# design.net
KiCad netlist of a schematic drawn in Altium Designer
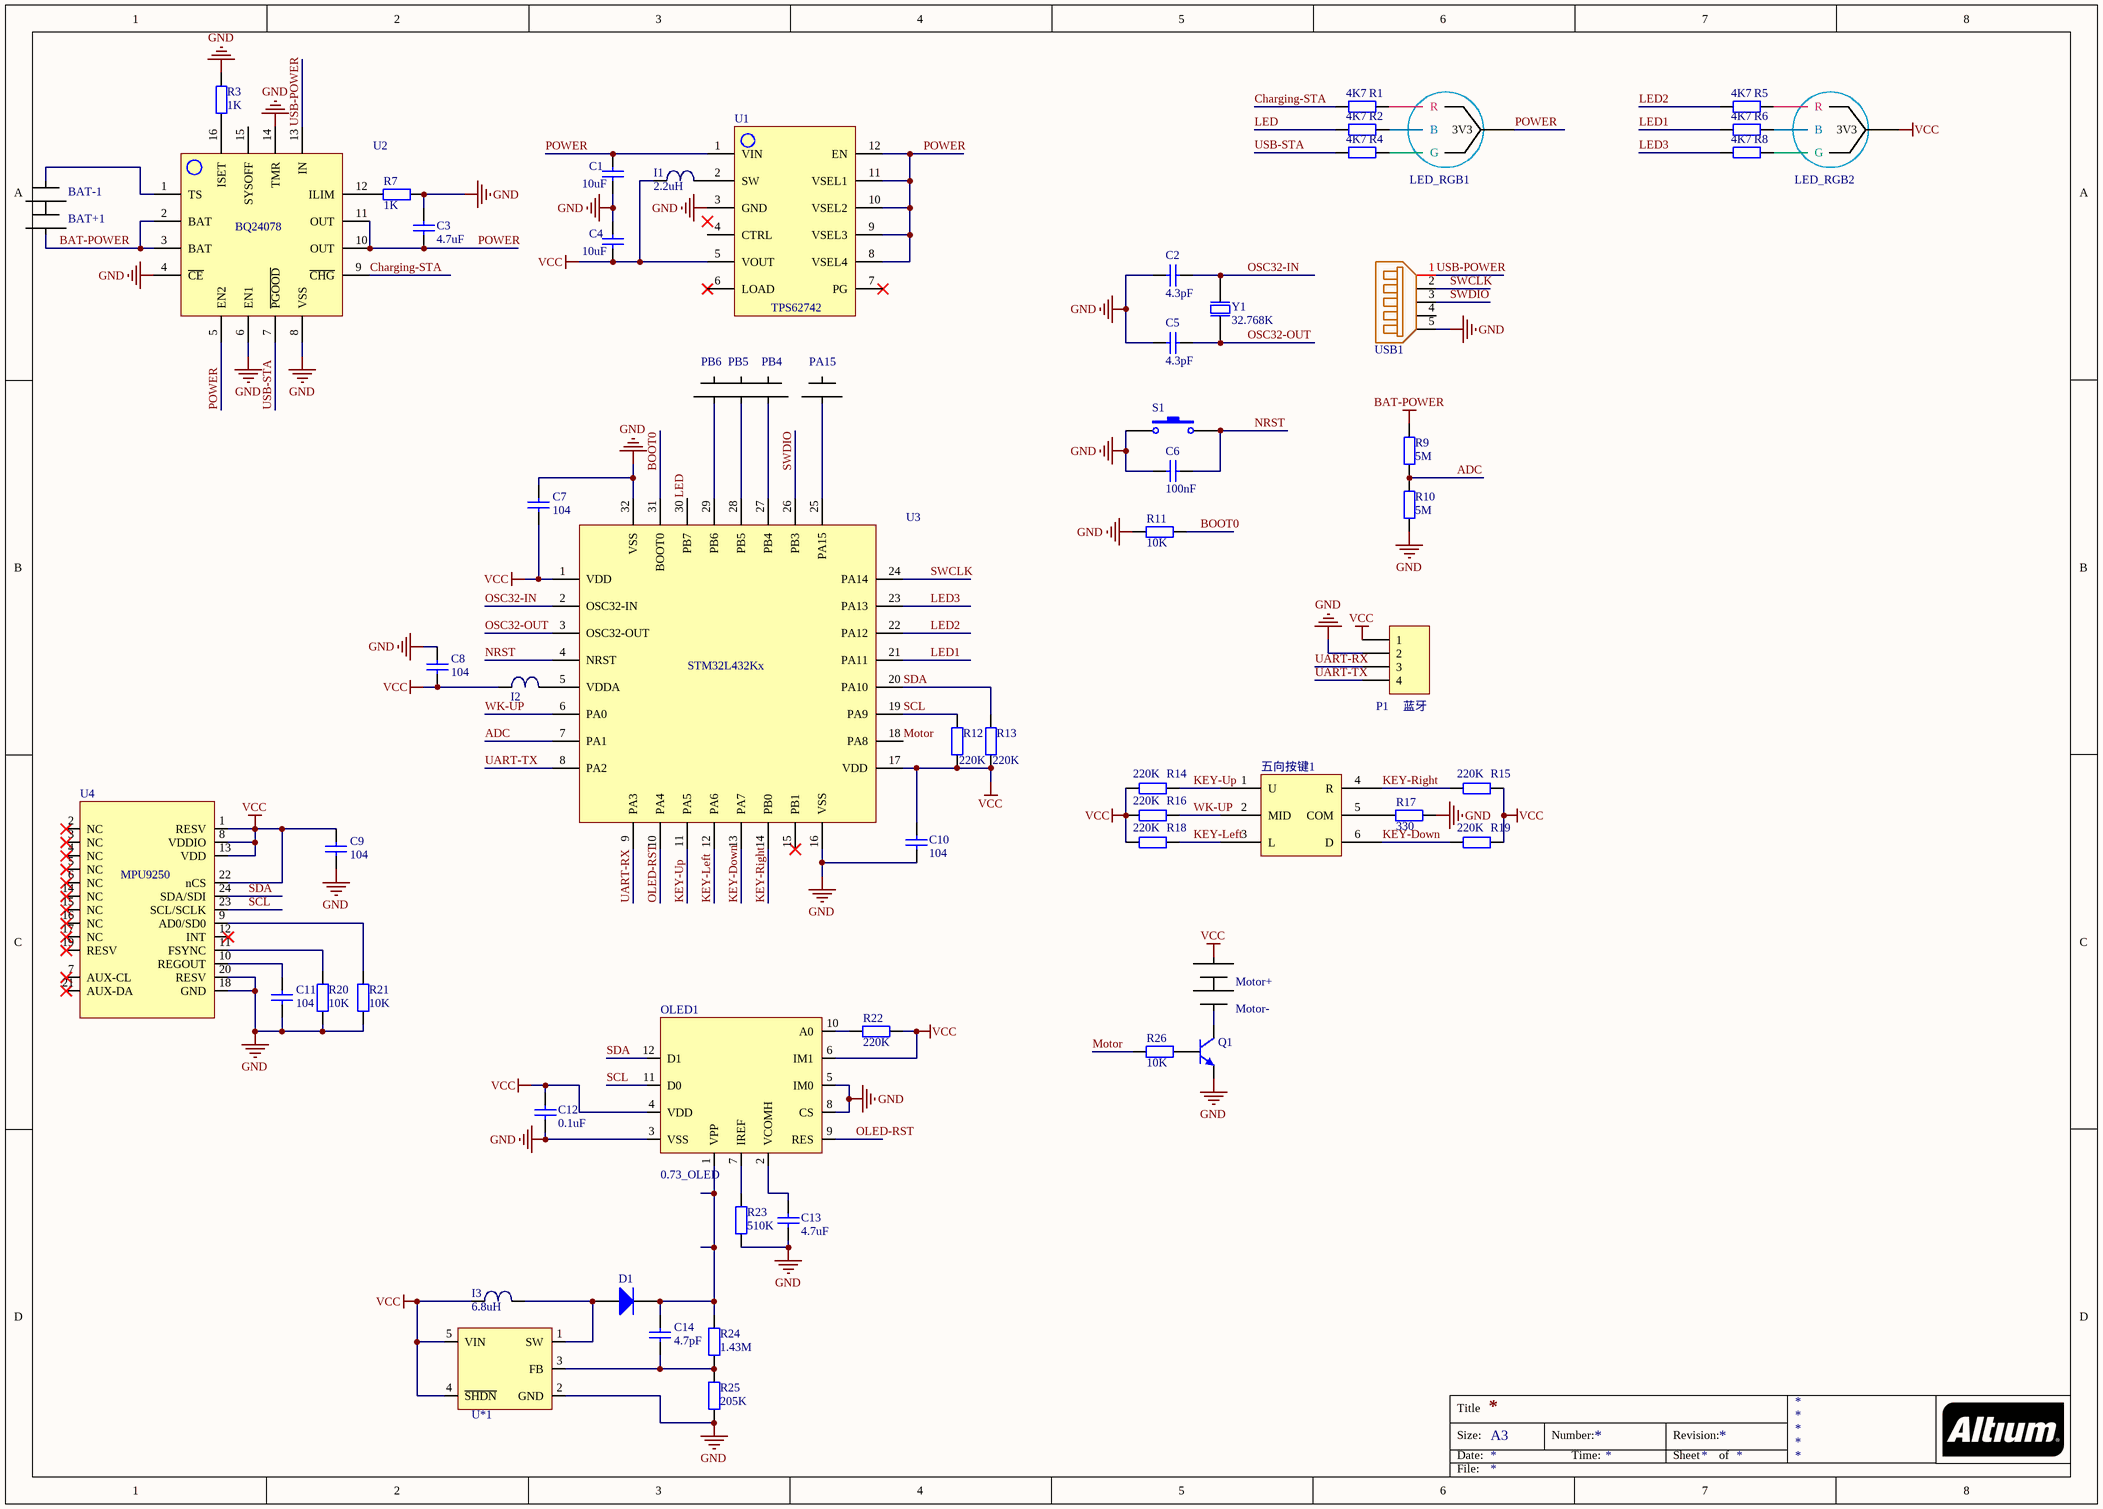
[diagram p0: 原理图.SchDoc]

(export (version "E")
  (design (tool "Eeschema 10.0.6"))
  (components
    (comp (ref "BAT+1") (value "BAT") (footprint "BAT+") (libsource (lib "原理图库") (part "BAT")))
    (comp (ref "BAT-1") (value "BAT") (footprint "BTA-") (libsource (lib "原理图库") (part "BAT")))
    (comp (ref "C1")
      (value "10uF")
      (footprint "1__0603-CAP_")
      (description "Capacitor")
      (libsource (lib "Miscellaneous Devices") (part "Cap"))
    )
    (comp (ref "C2")
      (value "4.3pF")
      (footprint "1__0603-CAP_")
      (description "Capacitor")
      (libsource (lib "Miscellaneous Devices") (part "Cap"))
    )
    (comp (ref "C3")
      (value "4.7uF")
      (footprint "1__0603-CAP_")
      (description "Capacitor")
      (libsource (lib "Miscellaneous Devices") (part "Cap"))
    )
    (comp (ref "C4")
      (value "10uF")
      (footprint "1__0603-CAP_")
      (description "Capacitor")
      (libsource (lib "Miscellaneous Devices") (part "Cap"))
    )
    (comp (ref "C5")
      (value "4.3pF")
      (footprint "1__0603-CAP_")
      (description "Capacitor")
      (libsource (lib "Miscellaneous Devices") (part "Cap"))
    )
    (comp (ref "C6")
      (value "100nF")
      (footprint "1__0603-CAP_")
      (description "Capacitor")
      (libsource (lib "Miscellaneous Devices") (part "Cap"))
    )
    (comp (ref "C7")
      (value "104")
      (footprint "1__0603-CAP_")
      (description "Capacitor")
      (libsource (lib "Miscellaneous Devices") (part "Cap"))
    )
    (comp (ref "C8")
      (value "104")
      (footprint "1__0603-CAP_")
      (description "Capacitor")
      (libsource (lib "Miscellaneous Devices") (part "Cap"))
    )
    (comp (ref "C9")
      (value "104")
      (footprint "1__0603-CAP_")
      (description "Capacitor")
      (libsource (lib "Miscellaneous Devices") (part "Cap"))
    )
    (comp (ref "C10")
      (value "104")
      (footprint "1__0603-CAP_")
      (description "Capacitor")
      (libsource (lib "Miscellaneous Devices") (part "Cap"))
    )
    (comp (ref "C11")
      (value "104")
      (footprint "1__0603-CAP_")
      (description "Capacitor")
      (libsource (lib "Miscellaneous Devices") (part "Cap"))
    )
    (comp (ref "C12")
      (value "0.1uF")
      (footprint "1__0603-CAP_")
      (description "Capacitor")
      (libsource (lib "Miscellaneous Devices") (part "Cap"))
    )
    (comp (ref "C13")
      (value "4.7uF")
      (footprint "1__0603-CAP_")
      (description "Capacitor")
      (libsource (lib "Miscellaneous Devices") (part "Cap"))
    )
    (comp (ref "C14")
      (value "4.7pF")
      (footprint "1__0603-CAP_")
      (description "Capacitor")
      (libsource (lib "Miscellaneous Devices") (part "Cap"))
    )
    (comp (ref "D1")
      (value "Diode")
      (footprint "二极管1206")
      (description "Default Diode")
      (fields (field (name "PUBLISHER") "Altium Limited"))
      (libsource (lib "Miscellaneous Devices") (part "Diode"))
    )
    (comp (ref "I1") (value "2.2uH") (footprint "1__0805_IND") (libsource (lib "常用原理图_by_K") (part "电感")))
    (comp (ref "I2") (value "100uH") (footprint "1__0603_Ind_") (libsource (lib "常用原理图_by_K") (part "电感")))
    (comp (ref "I3") (value "6.8uH") (footprint "0805_Ind") (libsource (lib "常用原理图_by_K") (part "电感")))
    (comp (ref "LED_RGB1")
      (value "L*")
      (footprint "1__LED_RGB")
      (libsource (lib "MotherBoard_Prototype") (part "LED_RGB"))
    )
    (comp (ref "LED_RGB2")
      (value "L*")
      (footprint "1__LED_RGB")
      (libsource (lib "MotherBoard_Prototype") (part "LED_RGB"))
    )
    (comp (ref "Motor+") (value "BAT") (footprint "BAT+") (libsource (lib "原理图库") (part "BAT")))
    (comp (ref "Motor-") (value "BAT") (footprint "BTA-") (libsource (lib "原理图库") (part "BAT")))
    (comp (ref "OLED1")
      (value "0.73_OLED")
      (footprint "0.73OLED")
      (libsource (lib "原理图库") (part "0.73_OLED"))
    )
    (comp (ref "P1")
      (value "蓝牙")
      (footprint "BT")
      (description "Header, 4-Pin")
      (libsource (lib "!)Miscellaneous Integrated Library") (part "Header 4"))
    )
    (comp (ref "PA15") (value "BAT") (footprint "BAT+") (libsource (lib "原理图库") (part "BAT")))
    (comp (ref "PB4") (value "BAT") (footprint "BAT+") (libsource (lib "原理图库") (part "BAT")))
    (comp (ref "PB5") (value "BAT") (footprint "BAT+") (libsource (lib "原理图库") (part "BAT")))
    (comp (ref "PB6") (value "BAT") (footprint "BAT+") (libsource (lib "原理图库") (part "BAT")))
    (comp (ref "Q1")
      (value "NPN-J3Y/Y1")
      (footprint "SOT23")
      (description "NPN Bipolar Transistor")
      (fields (field (name "PARTNUMBER") "BC817-40") (field (name "PUBLISHER") "Altium Limited"))
      (libsource (lib "!)Miscellaneous Integrated Library") (part "NPN BC817-40"))
    )
    (comp (ref "R1")
      (value "4K7")
      (footprint "1__0603-RES_")
      (description "Resistor")
      (libsource (lib "") (part "Res2_1"))
    )
    (comp (ref "R2")
      (value "4K7")
      (footprint "1__0603-RES_")
      (description "Resistor")
      (libsource (lib "") (part "Res2_1"))
    )
    (comp (ref "R3")
      (value "1K")
      (footprint "1__0603-RES_")
      (description "Resistor")
      (libsource (lib "Miscellaneous Devices") (part "Res2"))
    )
    (comp (ref "R4")
      (value "4K7")
      (footprint "1__0603-RES_")
      (description "Resistor")
      (libsource (lib "") (part "Res2_1"))
    )
    (comp (ref "R5")
      (value "4K7")
      (footprint "1__0603-RES_")
      (description "Resistor")
      (libsource (lib "") (part "Res2_1"))
    )
    (comp (ref "R6")
      (value "4K7")
      (footprint "1__0603-RES_")
      (description "Resistor")
      (libsource (lib "") (part "Res2_1"))
    )
    (comp (ref "R7")
      (value "1K")
      (footprint "1__0603-RES_")
      (description "Resistor")
      (libsource (lib "") (part "Res2_1"))
    )
    (comp (ref "R8")
      (value "4K7")
      (footprint "1__0603-RES_")
      (description "Resistor")
      (libsource (lib "") (part "Res2_1"))
    )
    (comp (ref "R9")
      (value "5M")
      (footprint "1__0603-RES_")
      (description "Resistor")
      (libsource (lib "Miscellaneous Devices") (part "Res2"))
    )
    (comp (ref "R10")
      (value "5M")
      (footprint "1__0603-RES_")
      (description "Resistor")
      (libsource (lib "Miscellaneous Devices") (part "Res2"))
    )
    (comp (ref "R11")
      (value "10K")
      (footprint "1__0603-RES_")
      (description "Resistor")
      (libsource (lib "") (part "Res2_1"))
    )
    (comp (ref "R12")
      (value "220K")
      (footprint "1__0603-RES_")
      (description "Resistor")
      (libsource (lib "") (part "Res2_3"))
    )
    (comp (ref "R13")
      (value "220K")
      (footprint "1__0603-RES_")
      (description "Resistor")
      (libsource (lib "") (part "Res2_3"))
    )
    (comp (ref "R14")
      (value "220K")
      (footprint "1__0603-RES_")
      (description "Resistor")
      (libsource (lib "") (part "Res2_2"))
    )
    (comp (ref "R15")
      (value "220K")
      (footprint "1__0603-RES_")
      (description "Resistor")
      (libsource (lib "") (part "Res2_2"))
    )
    (comp (ref "R16")
      (value "220K")
      (footprint "1__0603-RES_")
      (description "Resistor")
      (libsource (lib "") (part "Res2_2"))
    )
    (comp (ref "R17")
      (value "330")
      (footprint "1__0603-RES_")
      (description "Resistor")
      (libsource (lib "") (part "Res2_1"))
    )
    (comp (ref "R18")
      (value "220K")
      (footprint "1__0603-RES_")
      (description "Resistor")
      (libsource (lib "") (part "Res2_2"))
    )
    (comp (ref "R19")
      (value "220K")
      (footprint "1__0603-RES_")
      (description "Resistor")
      (libsource (lib "") (part "Res2_2"))
    )
    (comp (ref "R20")
      (value "10K")
      (footprint "1__0603-RES_")
      (description "Resistor")
      (libsource (lib "") (part "Res2_3"))
    )
    (comp (ref "R21")
      (value "10K")
      (footprint "1__0603-RES_")
      (description "Resistor")
      (libsource (lib "") (part "Res2_3"))
    )
    (comp (ref "R22")
      (value "220K")
      (footprint "1__0603-RES_")
      (description "Resistor")
      (libsource (lib "") (part "Res2_2"))
    )
    (comp (ref "R23")
      (value "510K")
      (footprint "1__0603-RES_")
      (description "Resistor")
      (libsource (lib "Miscellaneous Devices") (part "Res2"))
    )
    (comp (ref "R24")
      (value "1.43M")
      (footprint "1__0603-RES_")
      (description "Resistor")
      (libsource (lib "Miscellaneous Devices") (part "Res2"))
    )
    (comp (ref "R25")
      (value "205K")
      (footprint "1__0603-RES_")
      (description "Resistor")
      (libsource (lib "Miscellaneous Devices") (part "Res2"))
    )
    (comp (ref "R26")
      (value "10K")
      (footprint "1__0603-RES_")
      (description "Resistor")
      (libsource (lib "") (part "Res2_1"))
    )
    (comp (ref "S1")
      (value "~")
      (footprint "key3*4*2")
      (description "Switch")
      (libsource (lib "Miscellaneous Devices") (part "SW-PB"))
    )
    (comp (ref "U*1") (value "OLED升压") (footprint "1__SOT23-5") (libsource (lib "原理图库") (part "TPS61040")))
    (comp (ref "U1")
      (value "TPS62742")
      (footprint "TPS62742")
      (description "锂电池稳压")
      (libsource (lib "原理图库") (part "TPS62742"))
    )
    (comp (ref "U2")
      (value "BQ24078")
      (footprint "BQ24078")
      (description "充电芯片")
      (libsource (lib "原理图库") (part "BQ24078"))
    )
    (comp (ref "U3")
      (value "STM32L432Kx")
      (footprint "STM32L432")
      (description "单片机")
      (libsource (lib "原理图库") (part "STM32L432Kx"))
    )
    (comp (ref "U4")
      (value "MPU9250")
      (footprint "1__QFN3*3 (改1)")
      (libsource (lib "Schlib1") (part "MPU9250"))
    )
    (comp (ref "USB1")
      (value "USB-5P")
      (footprint "1__Micro USB 立贴_")
      (description "USB CONNECTOR")
      (libsource (lib "!)Miscellaneous Integrated Library") (part "USB-5P"))
    )
    (comp (ref "Y1")
      (value "32.768K")
      (footprint "OSC32")
      (description "Crystal Oscillator")
      (libsource (lib "!)Miscellaneous Integrated Library") (part "XTAL"))
    )
    (comp (ref "五向按键1") (value "五向按键") (footprint "1__五向按键_") (libsource (lib "没有的器件原理图") (part "五向按键")))
  )
  (nets
    (net (code "2") (name "/ADC") (class "Default")
      (node (ref "R10") (pin "1") (pinfunction "1_1") (pintype "passive"))
      (node (ref "R9") (pin "2") (pinfunction "2_2") (pintype "passive"))
      (node (ref "U3") (pin "7") (pinfunction "PA1_7") (pintype "passive"))
    )
    (net (code "3") (name "/BOOT0") (class "Default")
      (node (ref "R11") (pin "1") (pinfunction "1_1") (pintype "passive"))
      (node (ref "U3") (pin "31") (pinfunction "BOOT0_31") (pintype "passive"))
    )
    (net (code "4") (name "/Charging-STA") (class "Default")
      (node (ref "R1") (pin "2") (pinfunction "2_2") (pintype "passive"))
      (node (ref "U2") (pin "9") (pinfunction "~{CHG}_9") (pintype "passive"))
    )
    (net (code "5") (name "/KEY-Down") (class "Default")
      (node (ref "R19") (pin "1") (pinfunction "1_1") (pintype "passive"))
      (node (ref "U3") (pin "13") (pinfunction "PA7_13") (pintype "passive"))
      (node (ref "五向按键1") (pin "6") (pinfunction "D_6") (pintype "passive"))
    )
    (net (code "6") (name "/KEY-Left") (class "Default")
      (node (ref "R18") (pin "2") (pinfunction "2_2") (pintype "passive"))
      (node (ref "U3") (pin "12") (pinfunction "PA6_12") (pintype "passive"))
      (node (ref "五向按键1") (pin "3") (pinfunction "L_3") (pintype "passive"))
    )
    (net (code "7") (name "/KEY-Right") (class "Default")
      (node (ref "R15") (pin "1") (pinfunction "1_1") (pintype "passive"))
      (node (ref "U3") (pin "14") (pinfunction "PB0_14") (pintype "passive"))
      (node (ref "五向按键1") (pin "4") (pinfunction "R_4") (pintype "passive"))
    )
    (net (code "8") (name "/KEY-Up") (class "Default")
      (node (ref "R14") (pin "2") (pinfunction "2_2") (pintype "passive"))
      (node (ref "U3") (pin "11") (pinfunction "PA5_11") (pintype "passive"))
      (node (ref "五向按键1") (pin "1") (pinfunction "U_1") (pintype "passive"))
    )
    (net (code "9") (name "/LED") (class "Default")
      (node (ref "R2") (pin "2") (pinfunction "2_2") (pintype "passive"))
      (node (ref "U3") (pin "30") (pinfunction "PB7_30") (pintype "passive"))
    )
    (net (code "10") (name "/LED1") (class "Default")
      (node (ref "R6") (pin "2") (pinfunction "2_2") (pintype "passive"))
      (node (ref "U3") (pin "21") (pinfunction "PA11_21") (pintype "passive"))
    )
    (net (code "11") (name "/LED2") (class "Default")
      (node (ref "R5") (pin "2") (pinfunction "2_2") (pintype "passive"))
      (node (ref "U3") (pin "22") (pinfunction "PA12_22") (pintype "passive"))
    )
    (net (code "12") (name "/LED3") (class "Default")
      (node (ref "R8") (pin "2") (pinfunction "2_2") (pintype "passive"))
      (node (ref "U3") (pin "23") (pinfunction "PA13_23") (pintype "passive"))
    )
    (net (code "13") (name "/Motor") (class "Default")
      (node (ref "R26") (pin "2") (pinfunction "2_2") (pintype "passive"))
      (node (ref "U3") (pin "18") (pinfunction "PA8_18") (pintype "passive"))
    )
    (net (code "14") (name "/NRST") (class "Default")
      (node (ref "C6") (pin "2") (pinfunction "2_2") (pintype "passive"))
      (node (ref "S1") (pin "2") (pinfunction "2_2") (pintype "passive"))
      (node (ref "U3") (pin "4") (pinfunction "NRST_4") (pintype "passive"))
    )
    (net (code "15") (name "/OLED-RST") (class "Default")
      (node (ref "OLED1") (pin "9") (pinfunction "RES_9") (pintype "passive"))
      (node (ref "U3") (pin "10") (pinfunction "PA4_10") (pintype "passive"))
    )
    (net (code "16") (name "/OSC32-IN") (class "Default")
      (node (ref "C2") (pin "1") (pinfunction "1_1") (pintype "passive"))
      (node (ref "U3") (pin "2") (pinfunction "OSC32-IN_2") (pintype "passive"))
      (node (ref "Y1") (pin "2") (pinfunction "OSC2_2") (pintype "passive"))
    )
    (net (code "17") (name "/OSC32-OUT") (class "Default")
      (node (ref "C5") (pin "1") (pinfunction "1_1") (pintype "passive"))
      (node (ref "U3") (pin "3") (pinfunction "OSC32-OUT_3") (pintype "passive"))
      (node (ref "Y1") (pin "1") (pinfunction "OSC1_1") (pintype "passive"))
    )
    (net (code "18") (name "/POWER") (class "Default")
      (node (ref "C1") (pin "2") (pinfunction "2_2") (pintype "passive"))
      (node (ref "C3") (pin "1") (pinfunction "1_1") (pintype "passive"))
      (node (ref "LED_RGB1") (pin "2") (pinfunction "3V3_2") (pintype "passive"))
      (node (ref "U1") (pin "1") (pinfunction "VIN_1") (pintype "passive"))
      (node (ref "U1") (pin "10") (pinfunction "VSEL2_10") (pintype "passive"))
      (node (ref "U1") (pin "11") (pinfunction "VSEL1_11") (pintype "passive"))
      (node (ref "U1") (pin "12") (pinfunction "EN_12") (pintype "passive"))
      (node (ref "U1") (pin "8") (pinfunction "VSEL4_8") (pintype "passive"))
      (node (ref "U1") (pin "9") (pinfunction "VSEL3_9") (pintype "passive"))
      (node (ref "U2") (pin "10") (pinfunction "OUT_10") (pintype "passive"))
      (node (ref "U2") (pin "11") (pinfunction "OUT_11") (pintype "passive"))
      (node (ref "U2") (pin "5") (pinfunction "EN2_5") (pintype "passive"))
    )
    (net (code "19") (name "/SCL") (class "Default")
      (node (ref "OLED1") (pin "11") (pinfunction "D0_11") (pintype "passive"))
      (node (ref "R12") (pin "2") (pinfunction "2_2") (pintype "passive"))
      (node (ref "U3") (pin "19") (pinfunction "PA9_19") (pintype "passive"))
      (node (ref "U4") (pin "23") (pinfunction "SCL/SCLK_23") (pintype "passive"))
    )
    (net (code "20") (name "/SDA") (class "Default")
      (node (ref "OLED1") (pin "12") (pinfunction "D1_12") (pintype "passive"))
      (node (ref "R13") (pin "2") (pinfunction "2_2") (pintype "passive"))
      (node (ref "U3") (pin "20") (pinfunction "PA10_20") (pintype "passive"))
      (node (ref "U4") (pin "24") (pinfunction "SDA/SDI_24") (pintype "passive"))
    )
    (net (code "21") (name "/SWCLK") (class "Default")
      (node (ref "U3") (pin "24") (pinfunction "PA14_24") (pintype "passive"))
      (node (ref "USB1") (pin "2") (pinfunction "D-_2") (pintype "passive"))
    )
    (net (code "22") (name "/SWDIO") (class "Default")
      (node (ref "U3") (pin "26") (pinfunction "PB3_26") (pintype "passive"))
      (node (ref "USB1") (pin "3") (pinfunction "D+_3") (pintype "passive"))
    )
    (net (code "23") (name "/UART-RX") (class "Default")
      (node (ref "P1") (pin "3") (pinfunction "3_3") (pintype "passive"))
      (node (ref "U3") (pin "9") (pinfunction "PA3_9") (pintype "passive"))
    )
    (net (code "24") (name "/UART-TX") (class "Default")
      (node (ref "P1") (pin "4") (pinfunction "4_4") (pintype "passive"))
      (node (ref "U3") (pin "8") (pinfunction "PA2_8") (pintype "passive"))
    )
    (net (code "25") (name "/USB-POWER") (class "Default")
      (node (ref "U2") (pin "13") (pinfunction "IN_13") (pintype "passive"))
      (node (ref "USB1") (pin "1") (pinfunction "VBUS_1") (pintype "passive"))
    )
    (net (code "26") (name "/USB-STA") (class "Default")
      (node (ref "R4") (pin "2") (pinfunction "2_2") (pintype "passive"))
      (node (ref "U2") (pin "7") (pinfunction "~{PGOOD}_7") (pintype "passive"))
    )
    (net (code "27") (name "/WK-UP") (class "Default")
      (node (ref "R16") (pin "2") (pinfunction "2_2") (pintype "passive"))
      (node (ref "U3") (pin "6") (pinfunction "PA0_6") (pintype "passive"))
      (node (ref "五向按键1") (pin "2") (pinfunction "MID_2") (pintype "passive"))
    )
    (net (code "28") (name "BAT-POWER") (class "Default")
      (node (ref "BAT+1") (pin "1") (pintype "passive"))
      (node (ref "R9") (pin "1") (pinfunction "1_1") (pintype "passive"))
      (node (ref "U2") (pin "2") (pinfunction "BAT_2") (pintype "passive"))
      (node (ref "U2") (pin "3") (pinfunction "BAT_3") (pintype "passive"))
    )
    (net (code "29") (name "GND") (class "Default")
      (node (ref "C1") (pin "1") (pinfunction "1_1") (pintype "passive"))
      (node (ref "C10") (pin "2") (pinfunction "2_2") (pintype "passive"))
      (node (ref "C11") (pin "1") (pinfunction "1_1") (pintype "passive"))
      (node (ref "C12") (pin "2") (pinfunction "2_2") (pintype "passive"))
      (node (ref "C13") (pin "2") (pinfunction "2_2") (pintype "passive"))
      (node (ref "C2") (pin "2") (pinfunction "2_2") (pintype "passive"))
      (node (ref "C3") (pin "2") (pinfunction "2_2") (pintype "passive"))
      (node (ref "C4") (pin "2") (pinfunction "2_2") (pintype "passive"))
      (node (ref "C5") (pin "2") (pinfunction "2_2") (pintype "passive"))
      (node (ref "C6") (pin "1") (pinfunction "1_1") (pintype "passive"))
      (node (ref "C7") (pin "2") (pinfunction "2_2") (pintype "passive"))
      (node (ref "C8") (pin "2") (pinfunction "2_2") (pintype "passive"))
      (node (ref "C9") (pin "1") (pinfunction "1_1") (pintype "passive"))
      (node (ref "OLED1") (pin "3") (pinfunction "VSS_3") (pintype "passive"))
      (node (ref "OLED1") (pin "5") (pinfunction "IM0_5") (pintype "passive"))
      (node (ref "OLED1") (pin "8") (pinfunction "CS_8") (pintype "passive"))
      (node (ref "P1") (pin "2") (pinfunction "2_2") (pintype "passive"))
      (node (ref "Q1") (pin "2") (pinfunction "E_2") (pintype "passive"))
      (node (ref "R10") (pin "2") (pinfunction "2_2") (pintype "passive"))
      (node (ref "R11") (pin "2") (pinfunction "2_2") (pintype "passive"))
      (node (ref "R17") (pin "1") (pinfunction "1_1") (pintype "passive"))
      (node (ref "R20") (pin "1") (pinfunction "1_1") (pintype "passive"))
      (node (ref "R21") (pin "1") (pinfunction "1_1") (pintype "passive"))
      (node (ref "R23") (pin "2") (pinfunction "2_2") (pintype "passive"))
      (node (ref "R25") (pin "2") (pinfunction "2_2") (pintype "passive"))
      (node (ref "R3") (pin "1") (pinfunction "1_1") (pintype "passive"))
      (node (ref "R7") (pin "1") (pinfunction "1_1") (pintype "passive"))
      (node (ref "S1") (pin "1") (pinfunction "1_1") (pintype "passive"))
      (node (ref "U*1") (pin "2") (pinfunction "GND_2") (pintype "passive"))
      (node (ref "U1") (pin "3") (pinfunction "GND_3") (pintype "passive"))
      (node (ref "U2") (pin "14") (pinfunction "TMR_14") (pintype "passive"))
      (node (ref "U2") (pin "4") (pinfunction "~{CE}_4") (pintype "passive"))
      (node (ref "U2") (pin "6") (pinfunction "EN1_6") (pintype "passive"))
      (node (ref "U2") (pin "8") (pinfunction "VSS_8") (pintype "passive"))
      (node (ref "U3") (pin "16") (pinfunction "VSS_16") (pintype "passive"))
      (node (ref "U3") (pin "32") (pinfunction "VSS_32") (pintype "passive"))
      (node (ref "U4") (pin "18") (pinfunction "GND_18") (pintype "passive"))
      (node (ref "U4") (pin "20") (pinfunction "RESV_20") (pintype "passive"))
      (node (ref "USB1") (pin "5") (pinfunction "GND_5") (pintype "passive"))
    )
    (net (code "30") (name "Net-(BAT+1-Pad2)") (class "Default")
      (node (ref "BAT+1") (pin "2") (pintype "passive"))
      (node (ref "BAT-1") (pin "1") (pintype "passive"))
    )
    (net (code "31") (name "Net-(D1-A)") (class "Default")
      (node (ref "D1") (pin "1") (pinfunction "A_1") (pintype "passive"))
      (node (ref "I3") (pin "2") (pinfunction "2_2") (pintype "passive"))
      (node (ref "U*1") (pin "1") (pinfunction "SW_1") (pintype "passive"))
    )
    (net (code "32") (name "Net-(D1-K)") (class "Default")
      (node (ref "C14") (pin "2") (pinfunction "2_2") (pintype "passive"))
      (node (ref "D1") (pin "2") (pinfunction "K_2") (pintype "passive"))
      (node (ref "OLED1") (pin "1") (pinfunction "VPP_1") (pintype "passive"))
      (node (ref "R24") (pin "1") (pinfunction "1_1") (pintype "passive"))
    )
    (net (code "33") (name "Net-(LED_RGB1-B)") (class "Default")
      (node (ref "LED_RGB1") (pin "4") (pinfunction "B_4") (pintype "passive"))
      (node (ref "R2") (pin "1") (pinfunction "1_1") (pintype "passive"))
    )
    (net (code "34") (name "Net-(LED_RGB1-G)") (class "Default")
      (node (ref "LED_RGB1") (pin "3") (pinfunction "G_3") (pintype "passive"))
      (node (ref "R4") (pin "1") (pinfunction "1_1") (pintype "passive"))
    )
    (net (code "35") (name "Net-(LED_RGB1-R)") (class "Default")
      (node (ref "LED_RGB1") (pin "1") (pinfunction "R_1") (pintype "passive"))
      (node (ref "R1") (pin "1") (pinfunction "1_1") (pintype "passive"))
    )
    (net (code "36") (name "Net-(LED_RGB2-B)") (class "Default")
      (node (ref "LED_RGB2") (pin "4") (pinfunction "B_4") (pintype "passive"))
      (node (ref "R6") (pin "1") (pinfunction "1_1") (pintype "passive"))
    )
    (net (code "37") (name "Net-(LED_RGB2-G)") (class "Default")
      (node (ref "LED_RGB2") (pin "3") (pinfunction "G_3") (pintype "passive"))
      (node (ref "R8") (pin "1") (pinfunction "1_1") (pintype "passive"))
    )
    (net (code "38") (name "Net-(LED_RGB2-R)") (class "Default")
      (node (ref "LED_RGB2") (pin "1") (pinfunction "R_1") (pintype "passive"))
      (node (ref "R5") (pin "1") (pinfunction "1_1") (pintype "passive"))
    )
    (net (code "39") (name "Net-(Motor+-Pad2)") (class "Default")
      (node (ref "Motor+") (pin "2") (pintype "passive"))
      (node (ref "Motor-") (pin "1") (pintype "passive"))
    )
    (net (code "40") (name "Net-(OLED1-A0)") (class "Default")
      (node (ref "OLED1") (pin "10") (pinfunction "A0_10") (pintype "passive"))
      (node (ref "R22") (pin "1") (pinfunction "1_1") (pintype "passive"))
    )
    (net (code "41") (name "Net-(OLED1-IREF)") (class "Default")
      (node (ref "OLED1") (pin "7") (pinfunction "IREF_7") (pintype "passive"))
      (node (ref "R23") (pin "1") (pinfunction "1_1") (pintype "passive"))
    )
    (net (code "42") (name "Net-(OLED1-VCOMH)") (class "Default")
      (node (ref "C13") (pin "1") (pinfunction "1_1") (pintype "passive"))
      (node (ref "OLED1") (pin "2") (pinfunction "VCOMH_2") (pintype "passive"))
    )
    (net (code "43") (name "Net-(Q1-B)") (class "Default")
      (node (ref "Q1") (pin "1") (pinfunction "B_1") (pintype "passive"))
      (node (ref "R26") (pin "1") (pinfunction "1_1") (pintype "passive"))
    )
    (net (code "44") (name "Net-(Q1-C)") (class "Default")
      (node (ref "Motor-") (pin "2") (pintype "passive"))
      (node (ref "Q1") (pin "3") (pinfunction "C_3") (pintype "passive"))
    )
    (net (code "45") (name "Net-(U*1-FB)") (class "Default")
      (node (ref "C14") (pin "1") (pinfunction "1_1") (pintype "passive"))
      (node (ref "R24") (pin "2") (pinfunction "2_2") (pintype "passive"))
      (node (ref "R25") (pin "1") (pinfunction "1_1") (pintype "passive"))
      (node (ref "U*1") (pin "3") (pinfunction "FB_3") (pintype "passive"))
    )
    (net (code "46") (name "Net-(U1-SW)") (class "Default")
      (node (ref "I1") (pin "2") (pinfunction "2_2") (pintype "passive"))
      (node (ref "U1") (pin "2") (pinfunction "SW_2") (pintype "passive"))
    )
    (net (code "47") (name "Net-(U2-ILIM)") (class "Default")
      (node (ref "R7") (pin "2") (pinfunction "2_2") (pintype "passive"))
      (node (ref "U2") (pin "12") (pinfunction "ILIM_12") (pintype "passive"))
    )
    (net (code "48") (name "Net-(U2-ISET)") (class "Default")
      (node (ref "R3") (pin "2") (pinfunction "2_2") (pintype "passive"))
      (node (ref "U2") (pin "16") (pinfunction "ISET_16") (pintype "passive"))
    )
    (net (code "49") (name "Net-(U2-TS)") (class "Default")
      (node (ref "BAT-1") (pin "2") (pintype "passive"))
      (node (ref "U2") (pin "1") (pinfunction "TS_1") (pintype "passive"))
    )
    (net (code "50") (name "Net-(U3-PA15)") (class "Default")
      (node (ref "PA15") (pin "1") (pintype "passive"))
      (node (ref "U3") (pin "25") (pinfunction "PA15_25") (pintype "passive"))
    )
    (net (code "51") (name "Net-(U3-PB4)") (class "Default")
      (node (ref "PB4") (pin "1") (pintype "passive"))
      (node (ref "U3") (pin "27") (pinfunction "PB4_27") (pintype "passive"))
    )
    (net (code "52") (name "Net-(U3-PB5)") (class "Default")
      (node (ref "PB5") (pin "1") (pintype "passive"))
      (node (ref "U3") (pin "28") (pinfunction "PB5_28") (pintype "passive"))
    )
    (net (code "53") (name "Net-(U3-PB6)") (class "Default")
      (node (ref "PB6") (pin "1") (pintype "passive"))
      (node (ref "U3") (pin "29") (pinfunction "PB6_29") (pintype "passive"))
    )
    (net (code "54") (name "Net-(U3-VDDA)") (class "Default")
      (node (ref "I2") (pin "2") (pinfunction "2_2") (pintype "passive"))
      (node (ref "U3") (pin "5") (pinfunction "VDDA_5") (pintype "passive"))
    )
    (net (code "55") (name "Net-(U4-AD0{slash}SD0)") (class "Default")
      (node (ref "R21") (pin "2") (pinfunction "2_2") (pintype "passive"))
      (node (ref "U4") (pin "9") (pinfunction "AD0/SD0_9") (pintype "passive"))
    )
    (net (code "56") (name "Net-(U4-FSYNC)") (class "Default")
      (node (ref "R20") (pin "2") (pinfunction "2_2") (pintype "passive"))
      (node (ref "U4") (pin "11") (pinfunction "FSYNC_11") (pintype "passive"))
    )
    (net (code "57") (name "Net-(U4-REGOUT)") (class "Default")
      (node (ref "C11") (pin "2") (pinfunction "2_2") (pintype "passive"))
      (node (ref "U4") (pin "10") (pinfunction "REGOUT_10") (pintype "passive"))
    )
    (net (code "58") (name "Net-(五向按键1-COM)") (class "Default")
      (node (ref "R17") (pin "2") (pinfunction "2_2") (pintype "passive"))
      (node (ref "五向按键1") (pin "5") (pinfunction "COM_5") (pintype "passive"))
    )
    (net (code "59") (name "VCC") (class "Default")
      (node (ref "C10") (pin "1") (pinfunction "1_1") (pintype "passive"))
      (node (ref "C12") (pin "1") (pinfunction "1_1") (pintype "passive"))
      (node (ref "C4") (pin "1") (pinfunction "1_1") (pintype "passive"))
      (node (ref "C7") (pin "1") (pinfunction "1_1") (pintype "passive"))
      (node (ref "C8") (pin "1") (pinfunction "1_1") (pintype "passive"))
      (node (ref "C9") (pin "2") (pinfunction "2_2") (pintype "passive"))
      (node (ref "I1") (pin "1") (pinfunction "1_1") (pintype "passive"))
      (node (ref "I2") (pin "1") (pinfunction "1_1") (pintype "passive"))
      (node (ref "I3") (pin "1") (pinfunction "1_1") (pintype "passive"))
      (node (ref "LED_RGB2") (pin "2") (pinfunction "3V3_2") (pintype "passive"))
      (node (ref "Motor+") (pin "1") (pintype "passive"))
      (node (ref "OLED1") (pin "4") (pinfunction "VDD_4") (pintype "passive"))
      (node (ref "OLED1") (pin "6") (pinfunction "IM1_6") (pintype "passive"))
      (node (ref "P1") (pin "1") (pinfunction "1_1") (pintype "passive"))
      (node (ref "R12") (pin "1") (pinfunction "1_1") (pintype "passive"))
      (node (ref "R13") (pin "1") (pinfunction "1_1") (pintype "passive"))
      (node (ref "R14") (pin "1") (pinfunction "1_1") (pintype "passive"))
      (node (ref "R15") (pin "2") (pinfunction "2_2") (pintype "passive"))
      (node (ref "R16") (pin "1") (pinfunction "1_1") (pintype "passive"))
      (node (ref "R18") (pin "1") (pinfunction "1_1") (pintype "passive"))
      (node (ref "R19") (pin "2") (pinfunction "2_2") (pintype "passive"))
      (node (ref "R22") (pin "2") (pinfunction "2_2") (pintype "passive"))
      (node (ref "U*1") (pin "4") (pinfunction "~{SHDN}_4") (pintype "passive"))
      (node (ref "U*1") (pin "5") (pinfunction "VIN_5") (pintype "passive"))
      (node (ref "U1") (pin "5") (pinfunction "VOUT_5") (pintype "passive"))
      (node (ref "U3") (pin "1") (pinfunction "VDD_1") (pintype "passive"))
      (node (ref "U3") (pin "17") (pinfunction "VDD_17") (pintype "passive"))
      (node (ref "U4") (pin "1") (pinfunction "RESV_1") (pintype "passive"))
      (node (ref "U4") (pin "13") (pinfunction "VDD_13") (pintype "passive"))
      (node (ref "U4") (pin "22") (pinfunction "nCS_22") (pintype "passive"))
      (node (ref "U4") (pin "8") (pinfunction "VDDIO_8") (pintype "passive"))
    )
    (net (code "60") (name "unconnected-(PA15-Pad2)") (class "Default")
      (node (ref "PA15") (pin "2") (pintype "passive"))
    )
    (net (code "61") (name "unconnected-(PB4-Pad2)") (class "Default")
      (node (ref "PB4") (pin "2") (pintype "passive"))
    )
    (net (code "62") (name "unconnected-(PB5-Pad2)") (class "Default")
      (node (ref "PB5") (pin "2") (pintype "passive"))
    )
    (net (code "63") (name "unconnected-(PB6-Pad2)") (class "Default")
      (node (ref "PB6") (pin "2") (pintype "passive"))
    )
    (net (code "64") (name "unconnected-(U1-CTRL-Pad4)") (class "Default")
      (node (ref "U1") (pin "4") (pinfunction "CTRL_4") (pintype "passive"))
    )
    (net (code "65") (name "unconnected-(U1-LOAD-Pad6)") (class "Default")
      (node (ref "U1") (pin "6") (pinfunction "LOAD_6") (pintype "passive+no_connect"))
    )
    (net (code "66") (name "unconnected-(U1-PG-Pad7)") (class "Default")
      (node (ref "U1") (pin "7") (pinfunction "PG_7") (pintype "passive+no_connect"))
    )
    (net (code "67") (name "unconnected-(U2-SYSOFF-Pad15)") (class "Default")
      (node (ref "U2") (pin "15") (pinfunction "SYSOFF_15") (pintype "passive"))
    )
    (net (code "68") (name "unconnected-(U3-PB1-Pad15)") (class "Default")
      (node (ref "U3") (pin "15") (pinfunction "PB1_15") (pintype "passive+no_connect"))
    )
    (net (code "69") (name "unconnected-(U4-AUX-CL-Pad7)") (class "Default")
      (node (ref "U4") (pin "7") (pinfunction "AUX-CL_7") (pintype "passive+no_connect"))
    )
    (net (code "70") (name "unconnected-(U4-AUX-DA-Pad21)") (class "Default")
      (node (ref "U4") (pin "21") (pinfunction "AUX-DA_21") (pintype "passive+no_connect"))
    )
    (net (code "71") (name "unconnected-(U4-INT-Pad12)") (class "Default")
      (node (ref "U4") (pin "12") (pinfunction "INT_12") (pintype "passive+no_connect"))
    )
    (net (code "72") (name "unconnected-(U4-NC-Pad2)") (class "Default")
      (node (ref "U4") (pin "2") (pinfunction "NC_2") (pintype "passive+no_connect"))
    )
    (net (code "73") (name "unconnected-(U4-NC-Pad3)") (class "Default")
      (node (ref "U4") (pin "3") (pinfunction "NC_3") (pintype "passive+no_connect"))
    )
    (net (code "74") (name "unconnected-(U4-NC-Pad4)") (class "Default")
      (node (ref "U4") (pin "4") (pinfunction "NC_4") (pintype "passive+no_connect"))
    )
    (net (code "75") (name "unconnected-(U4-NC-Pad5)") (class "Default")
      (node (ref "U4") (pin "5") (pinfunction "NC_5") (pintype "passive+no_connect"))
    )
    (net (code "76") (name "unconnected-(U4-NC-Pad6)") (class "Default")
      (node (ref "U4") (pin "6") (pinfunction "NC_6") (pintype "passive+no_connect"))
    )
    (net (code "77") (name "unconnected-(U4-NC-Pad14)") (class "Default")
      (node (ref "U4") (pin "14") (pinfunction "NC_14") (pintype "passive+no_connect"))
    )
    (net (code "78") (name "unconnected-(U4-NC-Pad15)") (class "Default")
      (node (ref "U4") (pin "15") (pinfunction "NC_15") (pintype "passive+no_connect"))
    )
    (net (code "79") (name "unconnected-(U4-NC-Pad16)") (class "Default")
      (node (ref "U4") (pin "16") (pinfunction "NC_16") (pintype "passive+no_connect"))
    )
    (net (code "80") (name "unconnected-(U4-NC-Pad17)") (class "Default")
      (node (ref "U4") (pin "17") (pinfunction "NC_17") (pintype "passive+no_connect"))
    )
    (net (code "81") (name "unconnected-(U4-RESV-Pad19)") (class "Default")
      (node (ref "U4") (pin "19") (pinfunction "RESV_19") (pintype "passive+no_connect"))
    )
    (net (code "82") (name "unconnected-(USB1-ID-Pad4)") (class "Default")
      (node (ref "USB1") (pin "4") (pinfunction "ID_4") (pintype "passive"))
    )
  )
)
